# MCU_CORE.net
KiCad netlist of a schematic drawn in Altium Designer
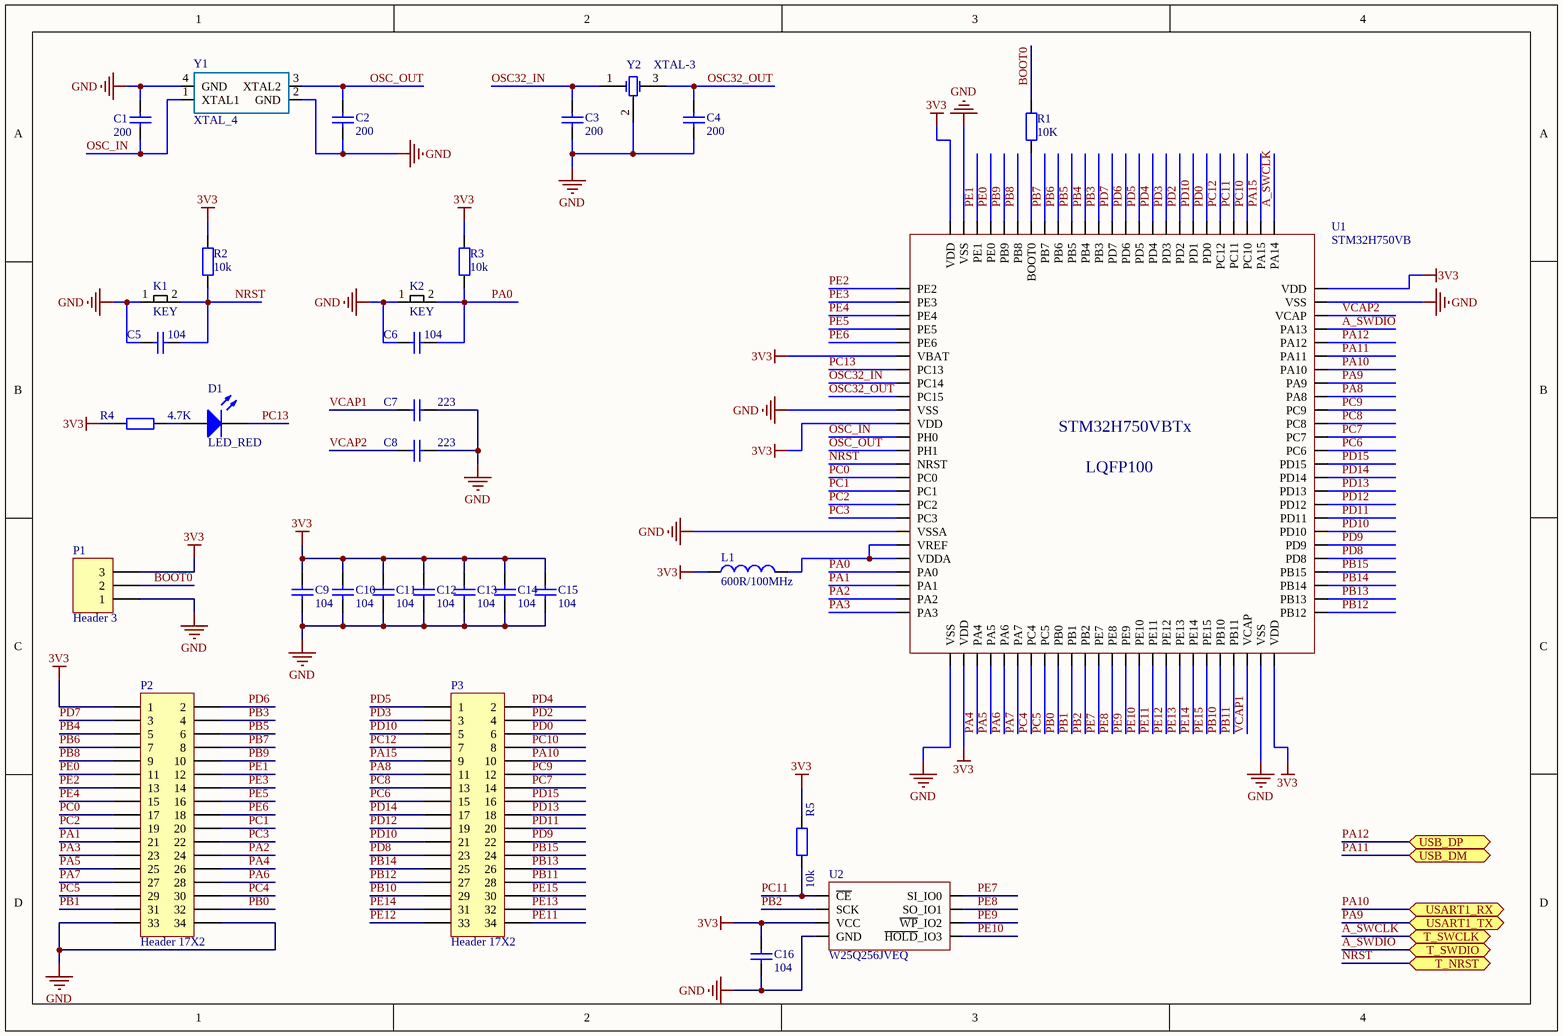
[diagram p0: MCU_CORE.SchDoc]

(export (version "E")
  (design (tool "Eeschema 10.0.6"))
  (components
    (comp (ref "C1") (value "200") (footprint "C_SOP_0603") (libsource (lib "lib-base") (part "Cap")))
    (comp (ref "C2") (value "200") (footprint "C_SOP_0603") (libsource (lib "lib-base") (part "Cap")))
    (comp (ref "C3") (value "200") (footprint "C_SOP_0603") (libsource (lib "lib-base") (part "Cap")))
    (comp (ref "C4") (value "200") (footprint "C_SOP_0603") (libsource (lib "lib-base") (part "Cap")))
    (comp (ref "C5") (value "104") (footprint "C_SOP_0603") (libsource (lib "lib-base") (part "Cap")))
    (comp (ref "C6") (value "104") (footprint "C_SOP_0603") (libsource (lib "lib-base") (part "Cap")))
    (comp (ref "C7") (value "223") (footprint "C_SOP_0603") (libsource (lib "lib-base") (part "Cap")))
    (comp (ref "C8") (value "223") (footprint "C_SOP_0603") (libsource (lib "lib-base") (part "Cap")))
    (comp (ref "C9") (value "104") (footprint "C_SOP_0603") (libsource (lib "lib-base") (part "Cap")))
    (comp (ref "C10") (value "104") (footprint "C_SOP_0603") (libsource (lib "lib-base") (part "Cap")))
    (comp (ref "C11") (value "104") (footprint "C_SOP_0603") (libsource (lib "lib-base") (part "Cap")))
    (comp (ref "C12") (value "104") (footprint "C_SOP_0603") (libsource (lib "lib-base") (part "Cap")))
    (comp (ref "C13") (value "104") (footprint "C_SOP_0603") (libsource (lib "lib-base") (part "Cap")))
    (comp (ref "C14") (value "104") (footprint "C_SOP_0603") (libsource (lib "lib-base") (part "Cap")))
    (comp (ref "C15") (value "104") (footprint "C_SOP_0603") (libsource (lib "lib-base") (part "Cap")))
    (comp (ref "C16") (value "104") (footprint "C_SOP_0603") (libsource (lib "lib-base") (part "Cap")))
    (comp (ref "D1")
      (value "LED_RED")
      (footprint "LED_0603_R")
      (description "发光二极管")
      (libsource (lib "lib-base") (part "LED"))
    )
    (comp (ref "K1") (value "KEY") (footprint "SW_PB_3X6") (libsource (lib "DG") (part "KEY")))
    (comp (ref "K2") (value "KEY") (footprint "SW_PB_3X6") (libsource (lib "DG") (part "KEY")))
    (comp (ref "L1") (value "600R/100MHz") (libsource (lib "lib-base") (part "L")))
    (comp (ref "P1")
      (value "Header 3")
      (footprint "HDR1X3")
      (description "Header, 3-Pin")
      (fields (field (name "PUBLISHER") "Altium Limited"))
      (libsource (lib "Miscellaneous Connectors") (part "Header 3"))
    )
    (comp (ref "P2")
      (value "Header 17X2")
      (footprint "HDR2X17")
      (description "Header, 17-Pin, Dual row")
      (fields (field (name "PUBLISHER") "Altium Limited"))
      (libsource (lib "Miscellaneous Connectors") (part "Header 17X2"))
    )
    (comp (ref "P3")
      (value "Header 17X2")
      (footprint "HDR2X17")
      (description "Header, 17-Pin, Dual row")
      (fields (field (name "PUBLISHER") "Altium Limited"))
      (libsource (lib "Miscellaneous Connectors") (part "Header 17X2"))
    )
    (comp (ref "R1") (value "10K") (footprint "R_SMD_0603") (libsource (lib "lib-base") (part "Res")))
    (comp (ref "R2") (value "10k") (footprint "R_SMD_0603") (libsource (lib "lib-base") (part "Res")))
    (comp (ref "R3") (value "10k") (footprint "R_SMD_0603") (libsource (lib "lib-base") (part "Res")))
    (comp (ref "R4") (value "4.7K") (footprint "R_SMD_0603") (libsource (lib "") (part "Res_1")))
    (comp (ref "R5") (value "10k") (footprint "R_SMD_0603") (libsource (lib "lib-base") (part "Res")))
    (comp (ref "U1")
      (value "STM32H750VB")
      (footprint "LQFP_100_14X14")
      (description "ST-MCU")
      (libsource (lib "lib-ic") (part "STM32H750VB"))
    )
    (comp (ref "U2")
      (value "W25Q256JVEQ")
      (footprint "SOIC_8")
      (description "QSPI-FLASH")
      (libsource (lib "lib-ic") (part "W25Q256JVEQ"))
    )
    (comp (ref "Y1") (value "XTAL_4") (footprint "XTAL_SMD_3225") (libsource (lib "DG") (part "XTAL_4")))
    (comp (ref "Y2") (value "XTAL-3") (footprint "XTAL_SMD_3215_2") (libsource (lib "DG") (part "XTAL-3")))
  )
  (nets
    (net (code "1") (name "/A_SWCLK") (class "Default")
      (node (ref "U1") (pin "76") (pinfunction "PA14_76") (pintype "passive"))
    )
    (net (code "2") (name "/A_SWDIO") (class "Default")
      (node (ref "U1") (pin "72") (pinfunction "PA13_72") (pintype "passive"))
    )
    (net (code "3") (name "/BOOT0") (class "Default")
      (node (ref "P1") (pin "2") (pinfunction "2_2") (pintype "passive"))
      (node (ref "R1") (pin "2") (pinfunction "2_2") (pintype "passive"))
    )
    (net (code "4") (name "/NRST") (class "Default")
      (node (ref "C5") (pin "1") (pinfunction "1_1") (pintype "passive"))
      (node (ref "K1") (pin "2") (pinfunction "*_2") (pintype "passive"))
      (node (ref "R2") (pin "1") (pinfunction "1_1") (pintype "passive"))
      (node (ref "U1") (pin "14") (pinfunction "NRST_14") (pintype "passive"))
    )
    (net (code "5") (name "/OSC32_IN") (class "Default")
      (node (ref "C3") (pin "2") (pinfunction "2_2") (pintype "passive"))
      (node (ref "U1") (pin "8") (pinfunction "PC14_8") (pintype "passive"))
      (node (ref "Y2") (pin "1") (pinfunction "OSC1_1") (pintype "passive"))
    )
    (net (code "6") (name "/OSC32_OUT") (class "Default")
      (node (ref "C4") (pin "2") (pinfunction "2_2") (pintype "passive"))
      (node (ref "U1") (pin "9") (pinfunction "PC15_9") (pintype "passive"))
      (node (ref "Y2") (pin "3") (pinfunction "OSC2_3") (pintype "passive"))
    )
    (net (code "7") (name "/OSC_IN") (class "Default")
      (node (ref "C1") (pin "1") (pinfunction "1_1") (pintype "passive"))
      (node (ref "U1") (pin "12") (pinfunction "PH0_12") (pintype "passive"))
      (node (ref "Y1") (pin "1") (pinfunction "XTAL1_1") (pintype "passive"))
    )
    (net (code "8") (name "/OSC_OUT") (class "Default")
      (node (ref "C2") (pin "2") (pinfunction "2_2") (pintype "passive"))
      (node (ref "U1") (pin "13") (pinfunction "PH1_13") (pintype "passive"))
      (node (ref "Y1") (pin "3") (pinfunction "XTAL2_3") (pintype "passive"))
    )
    (net (code "9") (name "/PA0") (class "Default")
      (node (ref "C6") (pin "1") (pinfunction "1_1") (pintype "passive"))
      (node (ref "K2") (pin "2") (pinfunction "*_2") (pintype "passive"))
      (node (ref "R3") (pin "1") (pinfunction "1_1") (pintype "passive"))
      (node (ref "U1") (pin "22") (pinfunction "PA0_22") (pintype "passive"))
    )
    (net (code "10") (name "/PA1") (class "Default")
      (node (ref "P2") (pin "21") (pinfunction "21_21") (pintype "passive"))
      (node (ref "U1") (pin "23") (pinfunction "PA1_23") (pintype "passive"))
    )
    (net (code "11") (name "/PA2") (class "Default")
      (node (ref "P2") (pin "24") (pinfunction "24_24") (pintype "passive"))
      (node (ref "U1") (pin "24") (pinfunction "PA2_24") (pintype "passive"))
    )
    (net (code "12") (name "/PA3") (class "Default")
      (node (ref "P2") (pin "23") (pinfunction "23_23") (pintype "passive"))
      (node (ref "U1") (pin "25") (pinfunction "PA3_25") (pintype "passive"))
    )
    (net (code "13") (name "/PA4") (class "Default")
      (node (ref "P2") (pin "26") (pinfunction "26_26") (pintype "passive"))
      (node (ref "U1") (pin "28") (pinfunction "PA4_28") (pintype "passive"))
    )
    (net (code "14") (name "/PA5") (class "Default")
      (node (ref "P2") (pin "25") (pinfunction "25_25") (pintype "passive"))
      (node (ref "U1") (pin "29") (pinfunction "PA5_29") (pintype "passive"))
    )
    (net (code "15") (name "/PA6") (class "Default")
      (node (ref "P2") (pin "28") (pinfunction "28_28") (pintype "passive"))
      (node (ref "U1") (pin "30") (pinfunction "PA6_30") (pintype "passive"))
    )
    (net (code "16") (name "/PA7") (class "Default")
      (node (ref "P2") (pin "27") (pinfunction "27_27") (pintype "passive"))
      (node (ref "U1") (pin "31") (pinfunction "PA7_31") (pintype "passive"))
    )
    (net (code "17") (name "/PA8") (class "Default")
      (node (ref "P3") (pin "11") (pinfunction "11_11") (pintype "passive"))
      (node (ref "U1") (pin "67") (pinfunction "PA8_67") (pintype "passive"))
    )
    (net (code "18") (name "/PA9") (class "Default")
      (node (ref "U1") (pin "68") (pinfunction "PA9_68") (pintype "passive"))
    )
    (net (code "19") (name "/PA10") (class "Default")
      (node (ref "P3") (pin "10") (pinfunction "10_10") (pintype "passive"))
      (node (ref "U1") (pin "69") (pinfunction "PA10_69") (pintype "passive"))
    )
    (net (code "20") (name "/PA11") (class "Default")
      (node (ref "U1") (pin "70") (pinfunction "PA11_70") (pintype "passive"))
    )
    (net (code "21") (name "/PA12") (class "Default")
      (node (ref "U1") (pin "71") (pinfunction "PA12_71") (pintype "passive"))
    )
    (net (code "22") (name "/PA15") (class "Default")
      (node (ref "P3") (pin "9") (pinfunction "9_9") (pintype "passive"))
      (node (ref "U1") (pin "77") (pinfunction "PA15_77") (pintype "passive"))
    )
    (net (code "23") (name "/PB0") (class "Default")
      (node (ref "P2") (pin "32") (pinfunction "32_32") (pintype "passive"))
      (node (ref "U1") (pin "34") (pinfunction "PB0_34") (pintype "passive"))
    )
    (net (code "24") (name "/PB1") (class "Default")
      (node (ref "P2") (pin "31") (pinfunction "31_31") (pintype "passive"))
      (node (ref "U1") (pin "35") (pinfunction "PB1_35") (pintype "passive"))
    )
    (net (code "25") (name "/PB2") (class "Default")
      (node (ref "U1") (pin "36") (pinfunction "PB2_36") (pintype "passive"))
      (node (ref "U2") (pin "6") (pinfunction "SCK_6") (pintype "passive"))
    )
    (net (code "26") (name "/PB3") (class "Default")
      (node (ref "P2") (pin "4") (pinfunction "4_4") (pintype "passive"))
      (node (ref "U1") (pin "89") (pinfunction "PB3_89") (pintype "passive"))
    )
    (net (code "27") (name "/PB4") (class "Default")
      (node (ref "P2") (pin "5") (pinfunction "5_5") (pintype "passive"))
      (node (ref "U1") (pin "90") (pinfunction "PB4_90") (pintype "passive"))
    )
    (net (code "28") (name "/PB5") (class "Default")
      (node (ref "P2") (pin "6") (pinfunction "6_6") (pintype "passive"))
      (node (ref "U1") (pin "91") (pinfunction "PB5_91") (pintype "passive"))
    )
    (net (code "29") (name "/PB6") (class "Default")
      (node (ref "P2") (pin "7") (pinfunction "7_7") (pintype "passive"))
      (node (ref "U1") (pin "92") (pinfunction "PB6_92") (pintype "passive"))
    )
    (net (code "30") (name "/PB7") (class "Default")
      (node (ref "P2") (pin "8") (pinfunction "8_8") (pintype "passive"))
      (node (ref "U1") (pin "93") (pinfunction "PB7_93") (pintype "passive"))
    )
    (net (code "31") (name "/PB8") (class "Default")
      (node (ref "P2") (pin "9") (pinfunction "9_9") (pintype "passive"))
      (node (ref "U1") (pin "95") (pinfunction "PB8_95") (pintype "passive"))
    )
    (net (code "32") (name "/PB9") (class "Default")
      (node (ref "P2") (pin "10") (pinfunction "10_10") (pintype "passive"))
      (node (ref "U1") (pin "96") (pinfunction "PB9_96") (pintype "passive"))
    )
    (net (code "33") (name "/PB10") (class "Default")
      (node (ref "P3") (pin "29") (pinfunction "29_29") (pintype "passive"))
      (node (ref "U1") (pin "46") (pinfunction "PB10_46") (pintype "passive"))
    )
    (net (code "34") (name "/PB11") (class "Default")
      (node (ref "P3") (pin "28") (pinfunction "28_28") (pintype "passive"))
      (node (ref "U1") (pin "47") (pinfunction "PB11_47") (pintype "passive"))
    )
    (net (code "35") (name "/PB12") (class "Default")
      (node (ref "P3") (pin "27") (pinfunction "27_27") (pintype "passive"))
      (node (ref "U1") (pin "51") (pinfunction "PB12_51") (pintype "passive"))
    )
    (net (code "36") (name "/PB13") (class "Default")
      (node (ref "P3") (pin "26") (pinfunction "26_26") (pintype "passive"))
      (node (ref "U1") (pin "52") (pinfunction "PB13_52") (pintype "passive"))
    )
    (net (code "37") (name "/PB14") (class "Default")
      (node (ref "P3") (pin "25") (pinfunction "25_25") (pintype "passive"))
      (node (ref "U1") (pin "53") (pinfunction "PB14_53") (pintype "passive"))
    )
    (net (code "38") (name "/PB15") (class "Default")
      (node (ref "P3") (pin "24") (pinfunction "24_24") (pintype "passive"))
      (node (ref "U1") (pin "54") (pinfunction "PB15_54") (pintype "passive"))
    )
    (net (code "39") (name "/PC0") (class "Default")
      (node (ref "P2") (pin "17") (pinfunction "17_17") (pintype "passive"))
      (node (ref "U1") (pin "15") (pinfunction "PC0_15") (pintype "passive"))
    )
    (net (code "40") (name "/PC1") (class "Default")
      (node (ref "P2") (pin "20") (pinfunction "20_20") (pintype "passive"))
      (node (ref "U1") (pin "16") (pinfunction "PC1_16") (pintype "passive"))
    )
    (net (code "41") (name "/PC2") (class "Default")
      (node (ref "P2") (pin "19") (pinfunction "19_19") (pintype "passive"))
      (node (ref "U1") (pin "17") (pinfunction "PC2_17") (pintype "passive"))
    )
    (net (code "42") (name "/PC3") (class "Default")
      (node (ref "P2") (pin "22") (pinfunction "22_22") (pintype "passive"))
      (node (ref "U1") (pin "18") (pinfunction "PC3_18") (pintype "passive"))
    )
    (net (code "43") (name "/PC4") (class "Default")
      (node (ref "P2") (pin "30") (pinfunction "30_30") (pintype "passive"))
      (node (ref "U1") (pin "32") (pinfunction "PC4_32") (pintype "passive"))
    )
    (net (code "44") (name "/PC5") (class "Default")
      (node (ref "P2") (pin "29") (pinfunction "29_29") (pintype "passive"))
      (node (ref "U1") (pin "33") (pinfunction "PC5_33") (pintype "passive"))
    )
    (net (code "45") (name "/PC6") (class "Default")
      (node (ref "P3") (pin "15") (pinfunction "15_15") (pintype "passive"))
      (node (ref "U1") (pin "63") (pinfunction "PC6_63") (pintype "passive"))
    )
    (net (code "46") (name "/PC7") (class "Default")
      (node (ref "P3") (pin "14") (pinfunction "14_14") (pintype "passive"))
      (node (ref "U1") (pin "64") (pinfunction "PC7_64") (pintype "passive"))
    )
    (net (code "47") (name "/PC8") (class "Default")
      (node (ref "P3") (pin "13") (pinfunction "13_13") (pintype "passive"))
      (node (ref "U1") (pin "65") (pinfunction "PC8_65") (pintype "passive"))
    )
    (net (code "48") (name "/PC9") (class "Default")
      (node (ref "P3") (pin "12") (pinfunction "12_12") (pintype "passive"))
      (node (ref "U1") (pin "66") (pinfunction "PC9_66") (pintype "passive"))
    )
    (net (code "49") (name "/PC10") (class "Default")
      (node (ref "P3") (pin "8") (pinfunction "8_8") (pintype "passive"))
      (node (ref "U1") (pin "78") (pinfunction "PC10_78") (pintype "passive"))
    )
    (net (code "50") (name "/PC11") (class "Default")
      (node (ref "R5") (pin "1") (pinfunction "1_1") (pintype "passive"))
      (node (ref "U1") (pin "79") (pinfunction "PC11_79") (pintype "passive"))
      (node (ref "U2") (pin "1") (pinfunction "~{CE}_1") (pintype "passive"))
    )
    (net (code "51") (name "/PC12") (class "Default")
      (node (ref "P3") (pin "7") (pinfunction "7_7") (pintype "passive"))
      (node (ref "U1") (pin "80") (pinfunction "PC12_80") (pintype "passive"))
    )
    (net (code "52") (name "/PC13") (class "Default")
      (node (ref "D1") (pin "2") (pinfunction "K_2") (pintype "passive"))
      (node (ref "U1") (pin "7") (pinfunction "PC13_7") (pintype "passive"))
    )
    (net (code "53") (name "/PD0") (class "Default")
      (node (ref "P3") (pin "6") (pinfunction "6_6") (pintype "passive"))
      (node (ref "U1") (pin "81") (pinfunction "PD0_81") (pintype "passive"))
    )
    (net (code "54") (name "/PD2") (class "Default")
      (node (ref "P3") (pin "4") (pinfunction "4_4") (pintype "passive"))
      (node (ref "U1") (pin "83") (pinfunction "PD2_83") (pintype "passive"))
    )
    (net (code "55") (name "/PD3") (class "Default")
      (node (ref "P3") (pin "3") (pinfunction "3_3") (pintype "passive"))
      (node (ref "U1") (pin "84") (pinfunction "PD3_84") (pintype "passive"))
    )
    (net (code "56") (name "/PD4") (class "Default")
      (node (ref "P3") (pin "2") (pinfunction "2_2") (pintype "passive"))
      (node (ref "U1") (pin "85") (pinfunction "PD4_85") (pintype "passive"))
    )
    (net (code "57") (name "/PD5") (class "Default")
      (node (ref "P3") (pin "1") (pinfunction "1_1") (pintype "passive"))
      (node (ref "U1") (pin "86") (pinfunction "PD5_86") (pintype "passive"))
    )
    (net (code "58") (name "/PD6") (class "Default")
      (node (ref "P2") (pin "2") (pinfunction "2_2") (pintype "passive"))
      (node (ref "U1") (pin "87") (pinfunction "PD6_87") (pintype "passive"))
    )
    (net (code "59") (name "/PD7") (class "Default")
      (node (ref "P2") (pin "3") (pinfunction "3_3") (pintype "passive"))
      (node (ref "U1") (pin "88") (pinfunction "PD7_88") (pintype "passive"))
    )
    (net (code "60") (name "/PD8") (class "Default")
      (node (ref "P3") (pin "23") (pinfunction "23_23") (pintype "passive"))
      (node (ref "U1") (pin "55") (pinfunction "PD8_55") (pintype "passive"))
    )
    (net (code "61") (name "/PD9") (class "Default")
      (node (ref "P3") (pin "22") (pinfunction "22_22") (pintype "passive"))
      (node (ref "U1") (pin "56") (pinfunction "PD9_56") (pintype "passive"))
    )
    (net (code "62") (name "/PD10") (class "Default")
      (node (ref "P3") (pin "21") (pinfunction "21_21") (pintype "passive"))
      (node (ref "P3") (pin "5") (pinfunction "5_5") (pintype "passive"))
      (node (ref "U1") (pin "57") (pinfunction "PD10_57") (pintype "passive"))
      (node (ref "U1") (pin "82") (pinfunction "PD1_82") (pintype "passive"))
    )
    (net (code "63") (name "/PD11") (class "Default")
      (node (ref "P3") (pin "20") (pinfunction "20_20") (pintype "passive"))
      (node (ref "U1") (pin "58") (pinfunction "PD11_58") (pintype "passive"))
    )
    (net (code "64") (name "/PD12") (class "Default")
      (node (ref "P3") (pin "19") (pinfunction "19_19") (pintype "passive"))
      (node (ref "U1") (pin "59") (pinfunction "PD12_59") (pintype "passive"))
    )
    (net (code "65") (name "/PD13") (class "Default")
      (node (ref "P3") (pin "18") (pinfunction "18_18") (pintype "passive"))
      (node (ref "U1") (pin "60") (pinfunction "PD13_60") (pintype "passive"))
    )
    (net (code "66") (name "/PD14") (class "Default")
      (node (ref "P3") (pin "17") (pinfunction "17_17") (pintype "passive"))
      (node (ref "U1") (pin "61") (pinfunction "PD14_61") (pintype "passive"))
    )
    (net (code "67") (name "/PD15") (class "Default")
      (node (ref "P3") (pin "16") (pinfunction "16_16") (pintype "passive"))
      (node (ref "U1") (pin "62") (pinfunction "PD15_62") (pintype "passive"))
    )
    (net (code "68") (name "/PE0") (class "Default")
      (node (ref "P2") (pin "11") (pinfunction "11_11") (pintype "passive"))
      (node (ref "U1") (pin "97") (pinfunction "PE0_97") (pintype "passive"))
    )
    (net (code "69") (name "/PE1") (class "Default")
      (node (ref "P2") (pin "12") (pinfunction "12_12") (pintype "passive"))
      (node (ref "U1") (pin "98") (pinfunction "PE1_98") (pintype "passive"))
    )
    (net (code "70") (name "/PE2") (class "Default")
      (node (ref "P2") (pin "13") (pinfunction "13_13") (pintype "passive"))
      (node (ref "U1") (pin "1") (pinfunction "PE2_1") (pintype "passive"))
    )
    (net (code "71") (name "/PE3") (class "Default")
      (node (ref "P2") (pin "14") (pinfunction "14_14") (pintype "passive"))
      (node (ref "U1") (pin "2") (pinfunction "PE3_2") (pintype "passive"))
    )
    (net (code "72") (name "/PE4") (class "Default")
      (node (ref "P2") (pin "15") (pinfunction "15_15") (pintype "passive"))
      (node (ref "U1") (pin "3") (pinfunction "PE4_3") (pintype "passive"))
    )
    (net (code "73") (name "/PE5") (class "Default")
      (node (ref "P2") (pin "16") (pinfunction "16_16") (pintype "passive"))
      (node (ref "U1") (pin "4") (pinfunction "PE5_4") (pintype "passive"))
    )
    (net (code "74") (name "/PE6") (class "Default")
      (node (ref "P2") (pin "18") (pinfunction "18_18") (pintype "passive"))
      (node (ref "U1") (pin "5") (pinfunction "PE6_5") (pintype "passive"))
    )
    (net (code "75") (name "/PE7") (class "Default")
      (node (ref "U1") (pin "37") (pinfunction "PE7_37") (pintype "passive"))
      (node (ref "U2") (pin "5") (pinfunction "SI_IO0_5") (pintype "passive"))
    )
    (net (code "76") (name "/PE8") (class "Default")
      (node (ref "U1") (pin "38") (pinfunction "PE8_38") (pintype "passive"))
      (node (ref "U2") (pin "2") (pinfunction "SO_IO1_2") (pintype "passive"))
    )
    (net (code "77") (name "/PE9") (class "Default")
      (node (ref "U1") (pin "39") (pinfunction "PE9_39") (pintype "passive"))
      (node (ref "U2") (pin "3") (pinfunction "~{WP}_IO2_3") (pintype "passive"))
    )
    (net (code "78") (name "/PE10") (class "Default")
      (node (ref "U1") (pin "40") (pinfunction "PE10_40") (pintype "passive"))
      (node (ref "U2") (pin "7") (pinfunction "~{HOLD}_IO3_7") (pintype "passive"))
    )
    (net (code "79") (name "/PE11") (class "Default")
      (node (ref "P3") (pin "34") (pinfunction "34_34") (pintype "passive"))
      (node (ref "U1") (pin "41") (pinfunction "PE11_41") (pintype "passive"))
    )
    (net (code "80") (name "/PE12") (class "Default")
      (node (ref "P3") (pin "33") (pinfunction "33_33") (pintype "passive"))
      (node (ref "U1") (pin "42") (pinfunction "PE12_42") (pintype "passive"))
    )
    (net (code "81") (name "/PE13") (class "Default")
      (node (ref "P3") (pin "32") (pinfunction "32_32") (pintype "passive"))
      (node (ref "U1") (pin "43") (pinfunction "PE13_43") (pintype "passive"))
    )
    (net (code "82") (name "/PE14") (class "Default")
      (node (ref "P3") (pin "31") (pinfunction "31_31") (pintype "passive"))
      (node (ref "U1") (pin "44") (pinfunction "PE14_44") (pintype "passive"))
    )
    (net (code "83") (name "/PE15") (class "Default")
      (node (ref "P3") (pin "30") (pinfunction "30_30") (pintype "passive"))
      (node (ref "U1") (pin "45") (pinfunction "PE15_45") (pintype "passive"))
    )
    (net (code "84") (name "/VCAP1") (class "Default")
      (node (ref "C7") (pin "2") (pinfunction "2_2") (pintype "passive"))
      (node (ref "U1") (pin "48") (pinfunction "VCAP_48") (pintype "passive"))
    )
    (net (code "85") (name "/VCAP2") (class "Default")
      (node (ref "C8") (pin "2") (pinfunction "2_2") (pintype "passive"))
      (node (ref "U1") (pin "73") (pinfunction "VCAP_73") (pintype "passive"))
    )
    (net (code "86") (name "3V3") (class "Default")
      (node (ref "C10") (pin "1") (pinfunction "1_1") (pintype "passive"))
      (node (ref "C11") (pin "1") (pinfunction "1_1") (pintype "passive"))
      (node (ref "C12") (pin "1") (pinfunction "1_1") (pintype "passive"))
      (node (ref "C13") (pin "1") (pinfunction "1_1") (pintype "passive"))
      (node (ref "C14") (pin "1") (pinfunction "1_1") (pintype "passive"))
      (node (ref "C15") (pin "1") (pinfunction "1_1") (pintype "passive"))
      (node (ref "C16") (pin "1") (pinfunction "1_1") (pintype "passive"))
      (node (ref "C9") (pin "1") (pinfunction "1_1") (pintype "passive"))
      (node (ref "L1") (pin "1") (pinfunction "1_1") (pintype "passive"))
      (node (ref "P1") (pin "3") (pinfunction "3_3") (pintype "passive"))
      (node (ref "P2") (pin "1") (pinfunction "1_1") (pintype "passive"))
      (node (ref "R2") (pin "2") (pinfunction "2_2") (pintype "passive"))
      (node (ref "R3") (pin "2") (pinfunction "2_2") (pintype "passive"))
      (node (ref "R4") (pin "2") (pinfunction "2_2") (pintype "passive"))
      (node (ref "R5") (pin "2") (pinfunction "2_2") (pintype "passive"))
      (node (ref "U1") (pin "100") (pinfunction "VDD_100") (pintype "passive"))
      (node (ref "U1") (pin "11") (pinfunction "VDD_11") (pintype "passive"))
      (node (ref "U1") (pin "27") (pinfunction "VDD_27") (pintype "passive"))
      (node (ref "U1") (pin "50") (pinfunction "VDD_50") (pintype "passive"))
      (node (ref "U1") (pin "6") (pinfunction "VBAT_6") (pintype "passive"))
      (node (ref "U1") (pin "75") (pinfunction "VDD_75") (pintype "passive"))
      (node (ref "U2") (pin "8") (pinfunction "VCC_8") (pintype "passive"))
    )
    (net (code "87") (name "GND") (class "Default")
      (node (ref "C1") (pin "2") (pinfunction "2_2") (pintype "passive"))
      (node (ref "C10") (pin "2") (pinfunction "2_2") (pintype "passive"))
      (node (ref "C11") (pin "2") (pinfunction "2_2") (pintype "passive"))
      (node (ref "C12") (pin "2") (pinfunction "2_2") (pintype "passive"))
      (node (ref "C13") (pin "2") (pinfunction "2_2") (pintype "passive"))
      (node (ref "C14") (pin "2") (pinfunction "2_2") (pintype "passive"))
      (node (ref "C15") (pin "2") (pinfunction "2_2") (pintype "passive"))
      (node (ref "C16") (pin "2") (pinfunction "2_2") (pintype "passive"))
      (node (ref "C2") (pin "1") (pinfunction "1_1") (pintype "passive"))
      (node (ref "C3") (pin "1") (pinfunction "1_1") (pintype "passive"))
      (node (ref "C4") (pin "1") (pinfunction "1_1") (pintype "passive"))
      (node (ref "C5") (pin "2") (pinfunction "2_2") (pintype "passive"))
      (node (ref "C6") (pin "2") (pinfunction "2_2") (pintype "passive"))
      (node (ref "C7") (pin "1") (pinfunction "1_1") (pintype "passive"))
      (node (ref "C8") (pin "1") (pinfunction "1_1") (pintype "passive"))
      (node (ref "C9") (pin "2") (pinfunction "2_2") (pintype "passive"))
      (node (ref "K1") (pin "1") (pinfunction "*_1") (pintype "passive"))
      (node (ref "K2") (pin "1") (pinfunction "*_1") (pintype "passive"))
      (node (ref "P1") (pin "1") (pinfunction "1_1") (pintype "passive"))
      (node (ref "P2") (pin "33") (pinfunction "33_33") (pintype "passive"))
      (node (ref "P2") (pin "34") (pinfunction "34_34") (pintype "passive"))
      (node (ref "U1") (pin "10") (pinfunction "VSS_10") (pintype "passive"))
      (node (ref "U1") (pin "19") (pinfunction "VSSA_19") (pintype "passive"))
      (node (ref "U1") (pin "26") (pinfunction "VSS_26") (pintype "passive"))
      (node (ref "U1") (pin "49") (pinfunction "VSS_49") (pintype "passive"))
      (node (ref "U1") (pin "74") (pinfunction "VSS_74") (pintype "passive"))
      (node (ref "U1") (pin "99") (pinfunction "VSS_99") (pintype "passive"))
      (node (ref "U2") (pin "4") (pinfunction "GND_4") (pintype "passive"))
      (node (ref "Y1") (pin "2") (pinfunction "GND_2") (pintype "passive"))
      (node (ref "Y1") (pin "4") (pinfunction "GND_4") (pintype "passive"))
      (node (ref "Y2") (pin "2") (pinfunction "OSC2_2") (pintype "passive"))
    )
    (net (code "88") (name "Net-(D1-A)") (class "Default")
      (node (ref "D1") (pin "1") (pinfunction "A_1") (pintype "passive"))
      (node (ref "R4") (pin "1") (pinfunction "1_1") (pintype "passive"))
    )
    (net (code "89") (name "Net-(U1-BOOT0)") (class "Default")
      (node (ref "R1") (pin "1") (pinfunction "1_1") (pintype "passive"))
      (node (ref "U1") (pin "94") (pinfunction "BOOT0_94") (pintype "passive"))
    )
    (net (code "90") (name "Net-(U1-VDDA)") (class "Default")
      (node (ref "L1") (pin "2") (pinfunction "2_2") (pintype "passive"))
      (node (ref "U1") (pin "20") (pinfunction "VREF_20") (pintype "passive"))
      (node (ref "U1") (pin "21") (pinfunction "VDDA_21") (pintype "passive"))
    )
  )
)
